# Analog_input.net
KiCad netlist of a schematic drawn in Altium Designer
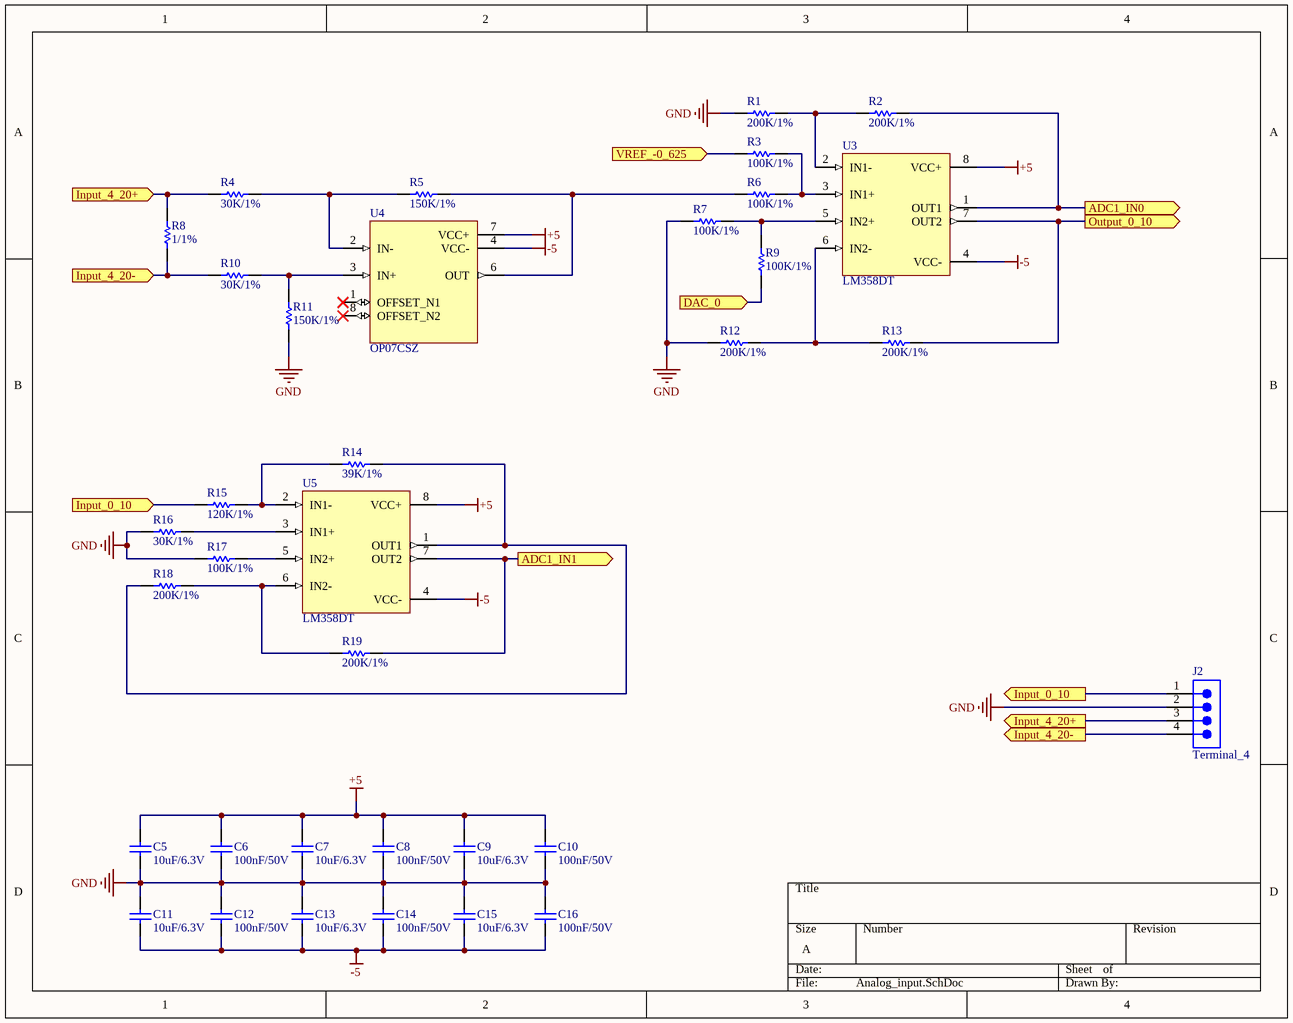
[diagram p0: Analog_input.SchDoc]

(export (version "E")
  (design (tool "Eeschema 10.0.6"))
  (components
    (comp (ref "C5")
      (value "10uF/6.3V")
      (footprint "CAP_0805")
      (libsource (lib "Iot_Flatform_lib_PTT") (part "Capacitor"))
    )
    (comp (ref "C6")
      (value "100nF/50V")
      (footprint "CAP_0805")
      (libsource (lib "Iot_Flatform_lib_PTT") (part "Capacitor"))
    )
    (comp (ref "C7")
      (value "10uF/6.3V")
      (footprint "CAP_0805")
      (libsource (lib "Iot_Flatform_lib_PTT") (part "Capacitor"))
    )
    (comp (ref "C8")
      (value "100nF/50V")
      (footprint "CAP_0805")
      (libsource (lib "Iot_Flatform_lib_PTT") (part "Capacitor"))
    )
    (comp (ref "C9")
      (value "10uF/6.3V")
      (footprint "CAP_0805")
      (libsource (lib "Iot_Flatform_lib_PTT") (part "Capacitor"))
    )
    (comp (ref "C10")
      (value "100nF/50V")
      (footprint "CAP_0805")
      (libsource (lib "Iot_Flatform_lib_PTT") (part "Capacitor"))
    )
    (comp (ref "C11")
      (value "10uF/6.3V")
      (footprint "CAP_0805")
      (libsource (lib "Iot_Flatform_lib_PTT") (part "Capacitor"))
    )
    (comp (ref "C12")
      (value "100nF/50V")
      (footprint "CAP_0805")
      (libsource (lib "Iot_Flatform_lib_PTT") (part "Capacitor"))
    )
    (comp (ref "C13")
      (value "10uF/6.3V")
      (footprint "CAP_0805")
      (libsource (lib "Iot_Flatform_lib_PTT") (part "Capacitor"))
    )
    (comp (ref "C14")
      (value "100nF/50V")
      (footprint "CAP_0805")
      (libsource (lib "Iot_Flatform_lib_PTT") (part "Capacitor"))
    )
    (comp (ref "C15")
      (value "10uF/6.3V")
      (footprint "CAP_0805")
      (libsource (lib "Iot_Flatform_lib_PTT") (part "Capacitor"))
    )
    (comp (ref "C16")
      (value "100nF/50V")
      (footprint "CAP_0805")
      (libsource (lib "Iot_Flatform_lib_PTT") (part "Capacitor"))
    )
    (comp (ref "J2")
      (value "Terminal_4")
      (footprint "TBL_4_3_81")
      (libsource (lib "Iot_Flatform_lib_PTT") (part "Terminal_4"))
    )
    (comp (ref "R1")
      (value "200K/1%")
      (footprint "RES_0805")
      (libsource (lib "Iot_Flatform_lib_PTT") (part "Resistor"))
    )
    (comp (ref "R2")
      (value "200K/1%")
      (footprint "RES_0805")
      (libsource (lib "Iot_Flatform_lib_PTT") (part "Resistor"))
    )
    (comp (ref "R3")
      (value "100K/1%")
      (footprint "RES_0805")
      (libsource (lib "Iot_Flatform_lib_PTT") (part "Resistor"))
    )
    (comp (ref "R4")
      (value "30K/1%")
      (footprint "RES_0805")
      (libsource (lib "Iot_Flatform_lib_PTT") (part "Resistor"))
    )
    (comp (ref "R5")
      (value "150K/1%")
      (footprint "RES_0603")
      (libsource (lib "Iot_Flatform_lib_PTT") (part "Resistor"))
    )
    (comp (ref "R6")
      (value "100K/1%")
      (footprint "RES_0805")
      (libsource (lib "Iot_Flatform_lib_PTT") (part "Resistor"))
    )
    (comp (ref "R7")
      (value "100K/1%")
      (footprint "RES_0805")
      (libsource (lib "Iot_Flatform_lib_PTT") (part "Resistor"))
    )
    (comp (ref "R8")
      (value "1/1%")
      (footprint "RES_0805")
      (libsource (lib "Iot_Flatform_lib_PTT") (part "Resistor"))
    )
    (comp (ref "R9")
      (value "100K/1%")
      (footprint "RES_0805")
      (libsource (lib "Iot_Flatform_lib_PTT") (part "Resistor"))
    )
    (comp (ref "R10")
      (value "30K/1%")
      (footprint "RES_0805")
      (libsource (lib "Iot_Flatform_lib_PTT") (part "Resistor"))
    )
    (comp (ref "R11")
      (value "150K/1%")
      (footprint "RES_0805")
      (libsource (lib "Iot_Flatform_lib_PTT") (part "Resistor"))
    )
    (comp (ref "R12")
      (value "200K/1%")
      (footprint "RES_0805")
      (libsource (lib "Iot_Flatform_lib_PTT") (part "Resistor"))
    )
    (comp (ref "R13")
      (value "200K/1%")
      (footprint "RES_0805")
      (libsource (lib "Iot_Flatform_lib_PTT") (part "Resistor"))
    )
    (comp (ref "R14")
      (value "39K/1%")
      (footprint "RES_0805")
      (libsource (lib "Iot_Flatform_lib_PTT") (part "Resistor"))
    )
    (comp (ref "R15")
      (value "120K/1%")
      (footprint "RES_0805")
      (libsource (lib "Iot_Flatform_lib_PTT") (part "Resistor"))
    )
    (comp (ref "R16")
      (value "30K/1%")
      (footprint "RES_0805")
      (libsource (lib "Iot_Flatform_lib_PTT") (part "Resistor"))
    )
    (comp (ref "R17")
      (value "100K/1%")
      (footprint "RES_0805")
      (libsource (lib "Iot_Flatform_lib_PTT") (part "Resistor"))
    )
    (comp (ref "R18")
      (value "200K/1%")
      (footprint "RES_0805")
      (libsource (lib "Iot_Flatform_lib_PTT") (part "Resistor"))
    )
    (comp (ref "R19")
      (value "200K/1%")
      (footprint "RES_0805")
      (libsource (lib "Iot_Flatform_lib_PTT") (part "Resistor"))
    )
    (comp (ref "U3")
      (value "LM358DT")
      (footprint "SOIC127P600X175-8N")
      (description "General Purpose Amplifier 2 Circuit 8-SO")
      (libsource (lib "Iot_Flatform_lib_PTT") (part "LM358DT"))
    )
    (comp (ref "U4")
      (value "OP07CSZ")
      (footprint "SOIC127P600X175-8N")
      (description "Low-Offset Voltage Operational Amplifier")
      (libsource (lib "Iot_Flatform_lib_PTT") (part "OP07CSZ"))
    )
    (comp (ref "U5")
      (value "LM358DT")
      (footprint "SOIC127P600X175-8N")
      (description "General Purpose Amplifier 2 Circuit 8-SO")
      (libsource (lib "Iot_Flatform_lib_PTT") (part "LM358DT"))
    )
  )
  (nets
    (net (code "1") (name "+5") (class "Default")
      (node (ref "C10") (pin "2") (pinfunction "2_2") (pintype "passive"))
      (node (ref "C5") (pin "2") (pinfunction "2_2") (pintype "passive"))
      (node (ref "C6") (pin "2") (pinfunction "2_2") (pintype "passive"))
      (node (ref "C7") (pin "2") (pinfunction "2_2") (pintype "passive"))
      (node (ref "C8") (pin "2") (pinfunction "2_2") (pintype "passive"))
      (node (ref "C9") (pin "2") (pinfunction "2_2") (pintype "passive"))
      (node (ref "U3") (pin "8") (pinfunction "VCC+_8") (pintype "power_in"))
      (node (ref "U4") (pin "7") (pinfunction "VCC+_7") (pintype "power_in"))
      (node (ref "U5") (pin "8") (pinfunction "VCC+_8") (pintype "power_in"))
    )
    (net (code "2") (name "-5") (class "Default")
      (node (ref "C11") (pin "1") (pinfunction "1_1") (pintype "passive"))
      (node (ref "C12") (pin "1") (pinfunction "1_1") (pintype "passive"))
      (node (ref "C13") (pin "1") (pinfunction "1_1") (pintype "passive"))
      (node (ref "C14") (pin "1") (pinfunction "1_1") (pintype "passive"))
      (node (ref "C15") (pin "1") (pinfunction "1_1") (pintype "passive"))
      (node (ref "C16") (pin "1") (pinfunction "1_1") (pintype "passive"))
      (node (ref "U3") (pin "4") (pinfunction "VCC-_4") (pintype "power_in"))
      (node (ref "U4") (pin "4") (pinfunction "VCC-_4") (pintype "power_in"))
      (node (ref "U5") (pin "4") (pinfunction "VCC-_4") (pintype "power_in"))
    )
    (net (code "3") (name "/ADC1_IN0") (class "Default")
      (node (ref "R2") (pin "2") (pinfunction "2_2") (pintype "passive"))
      (node (ref "U3") (pin "1") (pinfunction "OUT1_1") (pintype "output"))
    )
    (net (code "4") (name "/ADC1_IN1") (class "Default")
      (node (ref "R19") (pin "2") (pinfunction "2_2") (pintype "passive"))
      (node (ref "U5") (pin "7") (pinfunction "OUT2_7") (pintype "output"))
    )
    (net (code "5") (name "/DAC_0") (class "Default")
      (node (ref "R9") (pin "1") (pinfunction "1_1") (pintype "passive"))
    )
    (net (code "6") (name "/Input_0_10") (class "Default")
      (node (ref "J2") (pin "1") (pinfunction "1_1") (pintype "passive"))
      (node (ref "R15") (pin "1") (pinfunction "1_1") (pintype "passive"))
    )
    (net (code "7") (name "/Input_4_20+") (class "Default")
      (node (ref "J2") (pin "3") (pinfunction "3_3") (pintype "passive"))
      (node (ref "R4") (pin "1") (pinfunction "1_1") (pintype "passive"))
      (node (ref "R8") (pin "2") (pinfunction "2_2") (pintype "passive"))
    )
    (net (code "8") (name "/Input_4_20-") (class "Default")
      (node (ref "J2") (pin "4") (pinfunction "4_4") (pintype "passive"))
      (node (ref "R10") (pin "1") (pinfunction "1_1") (pintype "passive"))
      (node (ref "R8") (pin "1") (pinfunction "1_1") (pintype "passive"))
    )
    (net (code "9") (name "/Output_0_10") (class "Default")
      (node (ref "R13") (pin "2") (pinfunction "2_2") (pintype "passive"))
      (node (ref "U3") (pin "7") (pinfunction "OUT2_7") (pintype "output"))
    )
    (net (code "10") (name "/VREF_-0_625") (class "Default")
      (node (ref "R3") (pin "1") (pinfunction "1_1") (pintype "passive"))
    )
    (net (code "11") (name "GND") (class "Default")
      (node (ref "C10") (pin "1") (pinfunction "1_1") (pintype "passive"))
      (node (ref "C11") (pin "2") (pinfunction "2_2") (pintype "passive"))
      (node (ref "C12") (pin "2") (pinfunction "2_2") (pintype "passive"))
      (node (ref "C13") (pin "2") (pinfunction "2_2") (pintype "passive"))
      (node (ref "C14") (pin "2") (pinfunction "2_2") (pintype "passive"))
      (node (ref "C15") (pin "2") (pinfunction "2_2") (pintype "passive"))
      (node (ref "C16") (pin "2") (pinfunction "2_2") (pintype "passive"))
      (node (ref "C5") (pin "1") (pinfunction "1_1") (pintype "passive"))
      (node (ref "C6") (pin "1") (pinfunction "1_1") (pintype "passive"))
      (node (ref "C7") (pin "1") (pinfunction "1_1") (pintype "passive"))
      (node (ref "C8") (pin "1") (pinfunction "1_1") (pintype "passive"))
      (node (ref "C9") (pin "1") (pinfunction "1_1") (pintype "passive"))
      (node (ref "J2") (pin "2") (pinfunction "2_2") (pintype "passive"))
      (node (ref "R1") (pin "1") (pinfunction "1_1") (pintype "passive"))
      (node (ref "R11") (pin "1") (pinfunction "1_1") (pintype "passive"))
      (node (ref "R12") (pin "1") (pinfunction "1_1") (pintype "passive"))
      (node (ref "R16") (pin "1") (pinfunction "1_1") (pintype "passive"))
      (node (ref "R17") (pin "1") (pinfunction "1_1") (pintype "passive"))
      (node (ref "R7") (pin "1") (pinfunction "1_1") (pintype "passive"))
    )
    (net (code "12") (name "Net-(U3-IN1+)") (class "Default")
      (node (ref "R3") (pin "2") (pinfunction "2_2") (pintype "passive"))
      (node (ref "R6") (pin "2") (pinfunction "2_2") (pintype "passive"))
      (node (ref "U3") (pin "3") (pinfunction "IN1+_3") (pintype "input"))
    )
    (net (code "13") (name "Net-(U3-IN1-)") (class "Default")
      (node (ref "R1") (pin "2") (pinfunction "2_2") (pintype "passive"))
      (node (ref "R2") (pin "1") (pinfunction "1_1") (pintype "passive"))
      (node (ref "U3") (pin "2") (pinfunction "IN1-_2") (pintype "input"))
    )
    (net (code "14") (name "Net-(U3-IN2+)") (class "Default")
      (node (ref "R7") (pin "2") (pinfunction "2_2") (pintype "passive"))
      (node (ref "R9") (pin "2") (pinfunction "2_2") (pintype "passive"))
      (node (ref "U3") (pin "5") (pinfunction "IN2+_5") (pintype "input"))
    )
    (net (code "15") (name "Net-(U3-IN2-)") (class "Default")
      (node (ref "R12") (pin "2") (pinfunction "2_2") (pintype "passive"))
      (node (ref "R13") (pin "1") (pinfunction "1_1") (pintype "passive"))
      (node (ref "U3") (pin "6") (pinfunction "IN2-_6") (pintype "input"))
    )
    (net (code "16") (name "Net-(U4-IN+)") (class "Default")
      (node (ref "R10") (pin "2") (pinfunction "2_2") (pintype "passive"))
      (node (ref "R11") (pin "2") (pinfunction "2_2") (pintype "passive"))
      (node (ref "U4") (pin "3") (pinfunction "IN+_3") (pintype "input"))
    )
    (net (code "17") (name "Net-(U4-IN-)") (class "Default")
      (node (ref "R4") (pin "2") (pinfunction "2_2") (pintype "passive"))
      (node (ref "R5") (pin "1") (pinfunction "1_1") (pintype "passive"))
      (node (ref "U4") (pin "2") (pinfunction "IN-_2") (pintype "input"))
    )
    (net (code "18") (name "Net-(U4-OUT)") (class "Default")
      (node (ref "R5") (pin "2") (pinfunction "2_2") (pintype "passive"))
      (node (ref "R6") (pin "1") (pinfunction "1_1") (pintype "passive"))
      (node (ref "U4") (pin "6") (pinfunction "OUT_6") (pintype "output"))
    )
    (net (code "19") (name "Net-(U5-IN1+)") (class "Default")
      (node (ref "R16") (pin "2") (pinfunction "2_2") (pintype "passive"))
      (node (ref "U5") (pin "3") (pinfunction "IN1+_3") (pintype "input"))
    )
    (net (code "20") (name "Net-(U5-IN1-)") (class "Default")
      (node (ref "R14") (pin "1") (pinfunction "1_1") (pintype "passive"))
      (node (ref "R15") (pin "2") (pinfunction "2_2") (pintype "passive"))
      (node (ref "U5") (pin "2") (pinfunction "IN1-_2") (pintype "input"))
    )
    (net (code "21") (name "Net-(U5-IN2+)") (class "Default")
      (node (ref "R17") (pin "2") (pinfunction "2_2") (pintype "passive"))
      (node (ref "U5") (pin "5") (pinfunction "IN2+_5") (pintype "input"))
    )
    (net (code "22") (name "Net-(U5-IN2-)") (class "Default")
      (node (ref "R18") (pin "2") (pinfunction "2_2") (pintype "passive"))
      (node (ref "R19") (pin "1") (pinfunction "1_1") (pintype "passive"))
      (node (ref "U5") (pin "6") (pinfunction "IN2-_6") (pintype "input"))
    )
    (net (code "23") (name "Net-(U5-OUT1)") (class "Default")
      (node (ref "R14") (pin "2") (pinfunction "2_2") (pintype "passive"))
      (node (ref "R18") (pin "1") (pinfunction "1_1") (pintype "passive"))
      (node (ref "U5") (pin "1") (pinfunction "OUT1_1") (pintype "output"))
    )
    (net (code "24") (name "unconnected-(U4-OFFSET_N1-Pad1)") (class "Default")
      (node (ref "U4") (pin "1") (pinfunction "OFFSET_N1_1") (pintype "bidirectional+no_connect"))
    )
    (net (code "25") (name "unconnected-(U4-OFFSET_N2-Pad8)") (class "Default")
      (node (ref "U4") (pin "8") (pinfunction "OFFSET_N2_8") (pintype "bidirectional+no_connect"))
    )
  )
)
